# VCA.net
KiCad netlist of a schematic drawn in Altium Designer
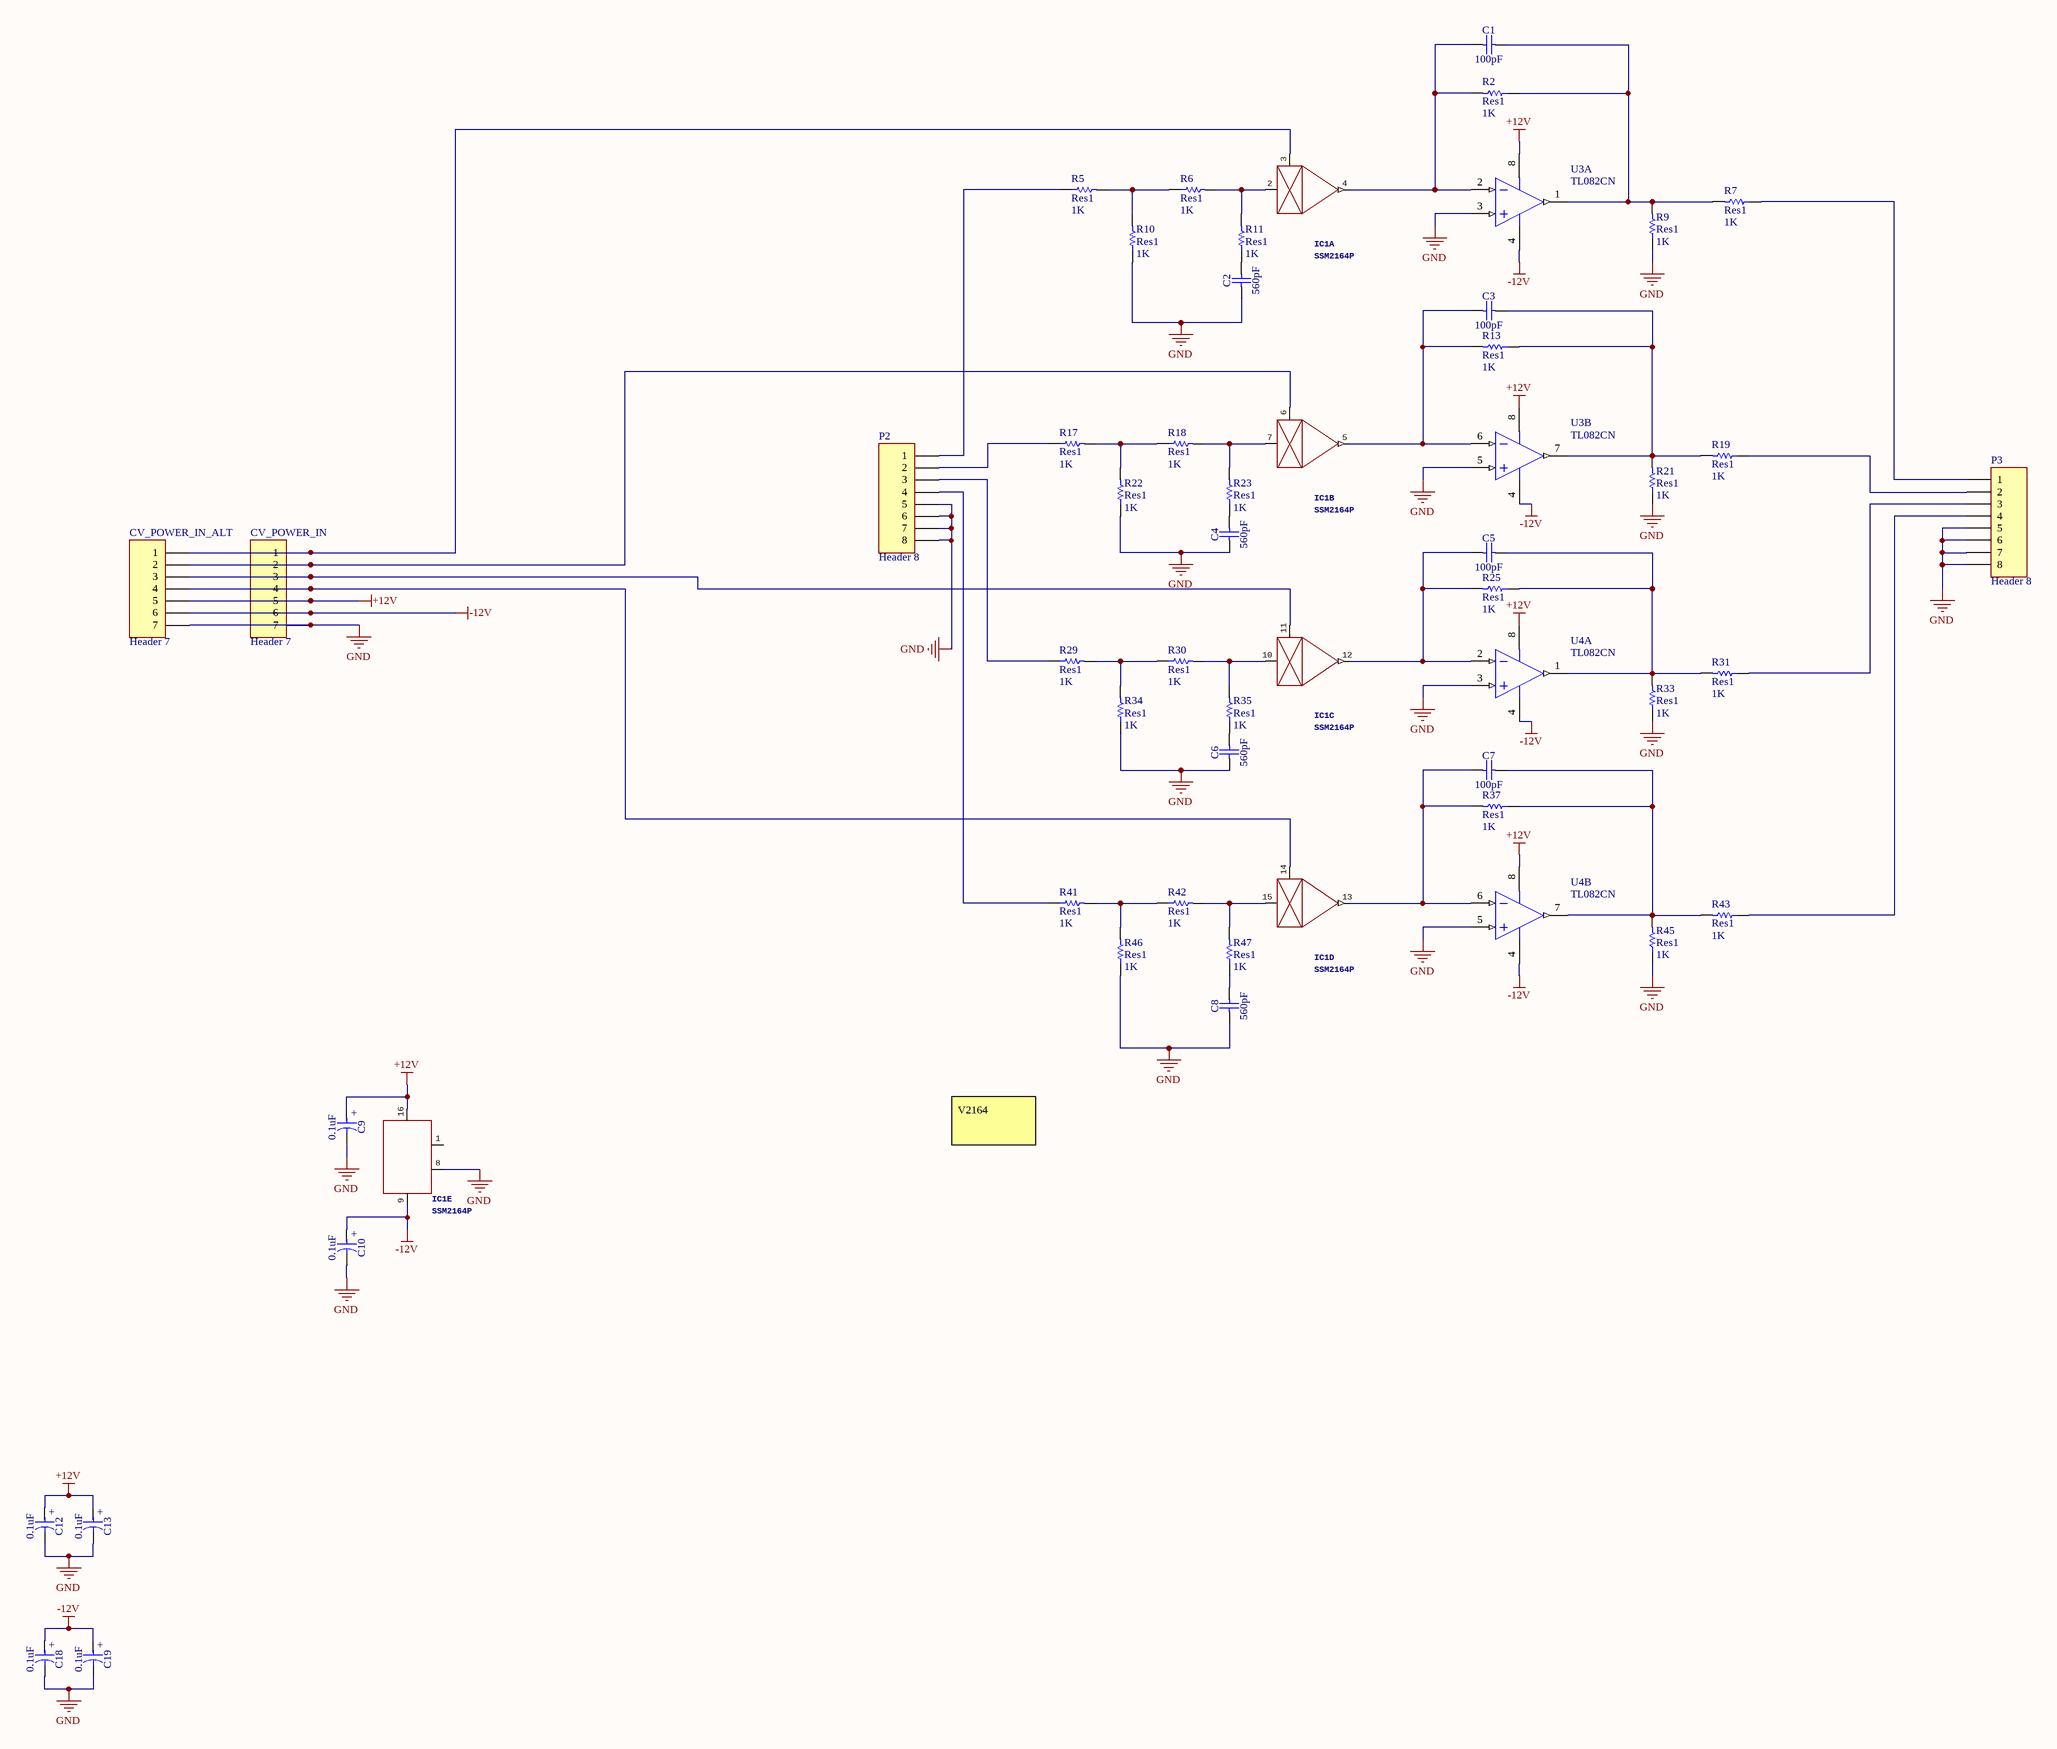
[diagram p0: VCA.SchDoc]

(export (version "E")
  (design (tool "Eeschema 10.0.6"))
  (components
    (comp (ref "C1")
      (value "100pF")
      (footprint "CAPRR508-254X381X584")
      (description "Non-polarised capacitor")
      (fields
        (field (name "PART NUMBER") "CCR_100PF_100V_5%_C0G_508-254X381X584")
        (field (name "VOLTAGE") "100VDC")
        (field (name "AUTHOR") "CERN DEM JLC")
      )
      (libsource (lib "Capacitors") (part "Capacitor - non polarized"))
    )
    (comp (ref "C2")
      (value "560pF")
      (footprint "CAPRR254-254X381X381")
      (description "Non-polarised capacitor")
      (fields
        (field (name "PART NUMBER") "CCR_560PF_100V_5%_C0G_254-254X381X381")
        (field (name "VOLTAGE") "100VDC")
        (field (name "AUTHOR") "CERN DEM JLC")
      )
      (libsource (lib "Capacitors") (part "Capacitor - non polarized"))
    )
    (comp (ref "C3")
      (value "100pF")
      (footprint "CAPRR508-254X381X584")
      (description "Non-polarised capacitor")
      (fields
        (field (name "PART NUMBER") "CCR_100PF_100V_5%_C0G_508-254X381X584")
        (field (name "VOLTAGE") "100VDC")
        (field (name "AUTHOR") "CERN DEM JLC")
      )
      (libsource (lib "Capacitors") (part "Capacitor - non polarized"))
    )
    (comp (ref "C4")
      (value "560pF")
      (footprint "CAPRR254-254X381X381")
      (description "Non-polarised capacitor")
      (fields
        (field (name "PART NUMBER") "CCR_560PF_100V_5%_C0G_254-254X381X381")
        (field (name "VOLTAGE") "100VDC")
        (field (name "AUTHOR") "CERN DEM JLC")
      )
      (libsource (lib "Capacitors") (part "Capacitor - non polarized"))
    )
    (comp (ref "C5")
      (value "100pF")
      (footprint "CAPRR508-254X381X584")
      (description "Non-polarised capacitor")
      (fields
        (field (name "PART NUMBER") "CCR_100PF_100V_5%_C0G_508-254X381X584")
        (field (name "VOLTAGE") "100VDC")
        (field (name "AUTHOR") "CERN DEM JLC")
      )
      (libsource (lib "Capacitors") (part "Capacitor - non polarized"))
    )
    (comp (ref "C6")
      (value "560pF")
      (footprint "CAPRR254-254X381X381")
      (description "Non-polarised capacitor")
      (fields
        (field (name "PART NUMBER") "CCR_560PF_100V_5%_C0G_254-254X381X381")
        (field (name "VOLTAGE") "100VDC")
        (field (name "AUTHOR") "CERN DEM JLC")
      )
      (libsource (lib "Capacitors") (part "Capacitor - non polarized"))
    )
    (comp (ref "C7")
      (value "100pF")
      (footprint "CAPRR508-254X381X584")
      (description "Non-polarised capacitor")
      (fields
        (field (name "PART NUMBER") "CCR_100PF_100V_5%_C0G_508-254X381X584")
        (field (name "VOLTAGE") "100VDC")
        (field (name "AUTHOR") "CERN DEM JLC")
      )
      (libsource (lib "Capacitors") (part "Capacitor - non polarized"))
    )
    (comp (ref "C8")
      (value "560pF")
      (footprint "CAPRR254-254X381X381")
      (description "Non-polarised capacitor")
      (fields
        (field (name "PART NUMBER") "CCR_560PF_100V_5%_C0G_254-254X381X381")
        (field (name "VOLTAGE") "100VDC")
        (field (name "AUTHOR") "CERN DEM JLC")
      )
      (libsource (lib "Capacitors") (part "Capacitor - non polarized"))
    )
    (comp (ref "C9")
      (value "0.1uF")
      (footprint "CAPPRB508-450x850")
      (description "Polarised capacitor")
      (fields
        (field (name "PART NUMBER") "CTEB_0.1UF_35V_10%_508-450X850")
        (field (name "VOLTAGE") "35V")
        (field (name "AUTHOR") "CERN DEM JLC")
      )
      (libsource (lib "Capacitors") (part "Capacitor - polarized"))
    )
    (comp (ref "C10")
      (value "0.1uF")
      (footprint "CAPPRB508-450x850")
      (description "Polarised capacitor")
      (fields
        (field (name "PART NUMBER") "CTEB_0.1UF_35V_10%_508-450X850")
        (field (name "VOLTAGE") "35V")
        (field (name "AUTHOR") "CERN DEM JLC")
      )
      (libsource (lib "Capacitors") (part "Capacitor - polarized"))
    )
    (comp (ref "C12")
      (value "0.1uF")
      (footprint "CAPPRB508-450x850")
      (description "Polarised capacitor")
      (fields
        (field (name "PART NUMBER") "CTEB_0.1UF_35V_10%_508-450X850")
        (field (name "VOLTAGE") "35V")
        (field (name "AUTHOR") "CERN DEM JLC")
      )
      (libsource (lib "Capacitors") (part "Capacitor - polarized"))
    )
    (comp (ref "C13")
      (value "0.1uF")
      (footprint "CAPPRB508-450x850")
      (description "Polarised capacitor")
      (fields
        (field (name "PART NUMBER") "CTEB_0.1UF_35V_10%_508-450X850")
        (field (name "VOLTAGE") "35V")
        (field (name "AUTHOR") "CERN DEM JLC")
      )
      (libsource (lib "Capacitors") (part "Capacitor - polarized"))
    )
    (comp (ref "C18")
      (value "0.1uF")
      (footprint "CAPPRB508-450x850")
      (description "Polarised capacitor")
      (fields
        (field (name "PART NUMBER") "CTEB_0.1UF_35V_10%_508-450X850")
        (field (name "VOLTAGE") "35V")
        (field (name "AUTHOR") "CERN DEM JLC")
      )
      (libsource (lib "Capacitors") (part "Capacitor - polarized"))
    )
    (comp (ref "C19")
      (value "0.1uF")
      (footprint "CAPPRB508-450x850")
      (description "Polarised capacitor")
      (fields
        (field (name "PART NUMBER") "CTEB_0.1UF_35V_10%_508-450X850")
        (field (name "VOLTAGE") "35V")
        (field (name "AUTHOR") "CERN DEM JLC")
      )
      (libsource (lib "Capacitors") (part "Capacitor - polarized"))
    )
    (comp (ref "CV_POWER_IN")
      (value "Header 7")
      (footprint "HDR1X7")
      (description "Header, 7-Pin")
      (fields (field (name "PUBLISHER") "Altium Limited"))
      (libsource (lib "Miscellaneous Connectors") (part "Header 7"))
    )
    (comp (ref "CV_POWER_IN_ALT")
      (value "Header 7")
      (footprint "HDR1X7")
      (description "Header, 7-Pin")
      (libsource (lib "Miscellaneous Connectors") (part "Header 7"))
    )
    (comp (ref "IC1") (value "SSM2164P") (footprint "DIL16") (libsource (lib "ssm2164_2") (part "SSM2164P")))
    (comp (ref "P2")
      (value "Header 8")
      (footprint "HDR1X8")
      (description "Header, 8-Pin")
      (fields (field (name "PUBLISHER") "Altium Limited"))
      (libsource (lib "") (part "Header 8_1"))
    )
    (comp (ref "P3")
      (value "Header 8")
      (footprint "HDR1X8")
      (description "Header, 8-Pin")
      (fields (field (name "PUBLISHER") "Altium Limited"))
      (libsource (lib "Miscellaneous Connectors") (part "Header 8"))
    )
    (comp (ref "R2")
      (value "Res1")
      (footprint "0207/2V")
      (description "Resistor")
      (fields (field (name "ALTIUM_VALUE") "1K") (field (name "PUBLISHER") "Altium Limited"))
      (libsource (lib "Miscellaneous Devices") (part "Res1"))
    )
    (comp (ref "R5")
      (value "Res1")
      (footprint "0207/2V")
      (description "Resistor")
      (fields (field (name "ALTIUM_VALUE") "1K") (field (name "PUBLISHER") "Altium Limited"))
      (libsource (lib "resistor") (part "Res1"))
    )
    (comp (ref "R6")
      (value "Res1")
      (footprint "0207/2V")
      (description "Resistor")
      (fields (field (name "ALTIUM_VALUE") "1K") (field (name "PUBLISHER") "Altium Limited"))
      (libsource (lib "Miscellaneous Devices") (part "Res1"))
    )
    (comp (ref "R7")
      (value "Res1")
      (footprint "0207/2V")
      (description "Resistor")
      (fields (field (name "ALTIUM_VALUE") "1K") (field (name "PUBLISHER") "Altium Limited"))
      (libsource (lib "Miscellaneous Devices") (part "Res1"))
    )
    (comp (ref "R9")
      (value "Res1")
      (footprint "0207/2V")
      (description "Resistor")
      (fields (field (name "ALTIUM_VALUE") "1K") (field (name "PUBLISHER") "Altium Limited"))
      (libsource (lib "Miscellaneous Devices") (part "Res1"))
    )
    (comp (ref "R10")
      (value "Res1")
      (footprint "0207/2V")
      (description "Resistor")
      (fields (field (name "ALTIUM_VALUE") "1K") (field (name "PUBLISHER") "Altium Limited"))
      (libsource (lib "Miscellaneous Devices") (part "Res1"))
    )
    (comp (ref "R11")
      (value "Res1")
      (footprint "0207/2V")
      (description "Resistor")
      (fields (field (name "ALTIUM_VALUE") "1K") (field (name "PUBLISHER") "Altium Limited"))
      (libsource (lib "Miscellaneous Devices") (part "Res1"))
    )
    (comp (ref "R13")
      (value "Res1")
      (footprint "0207/2V")
      (description "Resistor")
      (fields (field (name "ALTIUM_VALUE") "1K") (field (name "PUBLISHER") "Altium Limited"))
      (libsource (lib "Miscellaneous Devices") (part "Res1"))
    )
    (comp (ref "R17")
      (value "Res1")
      (footprint "0207/2V")
      (description "Resistor")
      (fields (field (name "ALTIUM_VALUE") "1K") (field (name "PUBLISHER") "Altium Limited"))
      (libsource (lib "Miscellaneous Devices") (part "Res1"))
    )
    (comp (ref "R18")
      (value "Res1")
      (footprint "0207/2V")
      (description "Resistor")
      (fields (field (name "ALTIUM_VALUE") "1K") (field (name "PUBLISHER") "Altium Limited"))
      (libsource (lib "Miscellaneous Devices") (part "Res1"))
    )
    (comp (ref "R19")
      (value "Res1")
      (footprint "0207/2V")
      (description "Resistor")
      (fields (field (name "ALTIUM_VALUE") "1K") (field (name "PUBLISHER") "Altium Limited"))
      (libsource (lib "Miscellaneous Devices") (part "Res1"))
    )
    (comp (ref "R21")
      (value "Res1")
      (footprint "0207/2V")
      (description "Resistor")
      (fields (field (name "ALTIUM_VALUE") "1K") (field (name "PUBLISHER") "Altium Limited"))
      (libsource (lib "Miscellaneous Devices") (part "Res1"))
    )
    (comp (ref "R22")
      (value "Res1")
      (footprint "0207/2V")
      (description "Resistor")
      (fields (field (name "ALTIUM_VALUE") "1K") (field (name "PUBLISHER") "Altium Limited"))
      (libsource (lib "Miscellaneous Devices") (part "Res1"))
    )
    (comp (ref "R23")
      (value "Res1")
      (footprint "0207/2V")
      (description "Resistor")
      (fields (field (name "ALTIUM_VALUE") "1K") (field (name "PUBLISHER") "Altium Limited"))
      (libsource (lib "Miscellaneous Devices") (part "Res1"))
    )
    (comp (ref "R25")
      (value "Res1")
      (footprint "0207/2V")
      (description "Resistor")
      (fields (field (name "ALTIUM_VALUE") "1K") (field (name "PUBLISHER") "Altium Limited"))
      (libsource (lib "Miscellaneous Devices") (part "Res1"))
    )
    (comp (ref "R29")
      (value "Res1")
      (footprint "0207/2V")
      (description "Resistor")
      (fields (field (name "ALTIUM_VALUE") "1K") (field (name "PUBLISHER") "Altium Limited"))
      (libsource (lib "Miscellaneous Devices") (part "Res1"))
    )
    (comp (ref "R30")
      (value "Res1")
      (footprint "0207/2V")
      (description "Resistor")
      (fields (field (name "ALTIUM_VALUE") "1K") (field (name "PUBLISHER") "Altium Limited"))
      (libsource (lib "Miscellaneous Devices") (part "Res1"))
    )
    (comp (ref "R31")
      (value "Res1")
      (footprint "0207/2V")
      (description "Resistor")
      (fields (field (name "ALTIUM_VALUE") "1K") (field (name "PUBLISHER") "Altium Limited"))
      (libsource (lib "Miscellaneous Devices") (part "Res1"))
    )
    (comp (ref "R33")
      (value "Res1")
      (footprint "0207/2V")
      (description "Resistor")
      (fields (field (name "ALTIUM_VALUE") "1K") (field (name "PUBLISHER") "Altium Limited"))
      (libsource (lib "Miscellaneous Devices") (part "Res1"))
    )
    (comp (ref "R34")
      (value "Res1")
      (footprint "0207/2V")
      (description "Resistor")
      (fields (field (name "ALTIUM_VALUE") "1K") (field (name "PUBLISHER") "Altium Limited"))
      (libsource (lib "Miscellaneous Devices") (part "Res1"))
    )
    (comp (ref "R35")
      (value "Res1")
      (footprint "0207/2V")
      (description "Resistor")
      (fields (field (name "ALTIUM_VALUE") "1K") (field (name "PUBLISHER") "Altium Limited"))
      (libsource (lib "Miscellaneous Devices") (part "Res1"))
    )
    (comp (ref "R37")
      (value "Res1")
      (footprint "0207/2V")
      (description "Resistor")
      (fields (field (name "ALTIUM_VALUE") "1K") (field (name "PUBLISHER") "Altium Limited"))
      (libsource (lib "Miscellaneous Devices") (part "Res1"))
    )
    (comp (ref "R41")
      (value "Res1")
      (footprint "0207/2V")
      (description "Resistor")
      (fields (field (name "ALTIUM_VALUE") "1K") (field (name "PUBLISHER") "Altium Limited"))
      (libsource (lib "Miscellaneous Devices") (part "Res1"))
    )
    (comp (ref "R42")
      (value "Res1")
      (footprint "0207/2V")
      (description "Resistor")
      (fields (field (name "ALTIUM_VALUE") "1K") (field (name "PUBLISHER") "Altium Limited"))
      (libsource (lib "Miscellaneous Devices") (part "Res1"))
    )
    (comp (ref "R43")
      (value "Res1")
      (footprint "0207/2V")
      (description "Resistor")
      (fields (field (name "ALTIUM_VALUE") "1K") (field (name "PUBLISHER") "Altium Limited"))
      (libsource (lib "Miscellaneous Devices") (part "Res1"))
    )
    (comp (ref "R45")
      (value "Res1")
      (footprint "0207/2V")
      (description "Resistor")
      (fields (field (name "ALTIUM_VALUE") "1K") (field (name "PUBLISHER") "Altium Limited"))
      (libsource (lib "Miscellaneous Devices") (part "Res1"))
    )
    (comp (ref "R46")
      (value "Res1")
      (footprint "0207/2V")
      (description "Resistor")
      (fields (field (name "ALTIUM_VALUE") "1K") (field (name "PUBLISHER") "Altium Limited"))
      (libsource (lib "Miscellaneous Devices") (part "Res1"))
    )
    (comp (ref "R47")
      (value "Res1")
      (footprint "0207/2V")
      (description "Resistor")
      (fields (field (name "ALTIUM_VALUE") "1K") (field (name "PUBLISHER") "Altium Limited"))
      (libsource (lib "Miscellaneous Devices") (part "Res1"))
    )
    (comp (ref "U3")
      (value "TL082CN")
      (footprint "STM-N8")
      (fields (field (name "MANUFACTURER") "STMicroelectronics"))
      (libsource (lib "Altium Content Vault") (part "STM-TL082-N8"))
    )
    (comp (ref "U4")
      (value "TL082CN")
      (footprint "STM-N8")
      (fields (field (name "MANUFACTURER") "STMicroelectronics"))
      (libsource (lib "Altium Content Vault") (part "STM-TL082-N8"))
    )
  )
  (nets
    (net (code "1") (name "+12V") (class "Default")
      (node (ref "C12") (pin "1") (pinfunction "1_1") (pintype "passive"))
      (node (ref "C13") (pin "1") (pinfunction "1_1") (pintype "passive"))
      (node (ref "C9") (pin "1") (pinfunction "1_1") (pintype "passive"))
      (node (ref "CV_POWER_IN") (pin "5") (pinfunction "5_5") (pintype "passive"))
      (node (ref "CV_POWER_IN_ALT") (pin "5") (pinfunction "5_5") (pintype "passive"))
      (node (ref "IC1") (pin "16") (pinfunction "V+_16") (pintype "power_in"))
      (node (ref "U3") (pin "8") (pinfunction "VCC+_8") (pintype "power_in"))
      (node (ref "U4") (pin "8") (pinfunction "VCC+_8") (pintype "power_in"))
    )
    (net (code "2") (name "-12V") (class "Default")
      (node (ref "C10") (pin "1") (pinfunction "1_1") (pintype "passive"))
      (node (ref "C18") (pin "1") (pinfunction "1_1") (pintype "passive"))
      (node (ref "C19") (pin "1") (pinfunction "1_1") (pintype "passive"))
      (node (ref "CV_POWER_IN") (pin "6") (pinfunction "6_6") (pintype "passive"))
      (node (ref "CV_POWER_IN_ALT") (pin "6") (pinfunction "6_6") (pintype "passive"))
      (node (ref "IC1") (pin "9") (pinfunction "V-_9") (pintype "power_in"))
      (node (ref "U3") (pin "4") (pinfunction "VCC-_4") (pintype "power_in"))
      (node (ref "U4") (pin "4") (pinfunction "VCC-_4") (pintype "power_in"))
    )
    (net (code "3") (name "GND") (class "Default")
      (node (ref "C10") (pin "2") (pinfunction "2_2") (pintype "passive"))
      (node (ref "C12") (pin "2") (pinfunction "2_2") (pintype "passive"))
      (node (ref "C13") (pin "2") (pinfunction "2_2") (pintype "passive"))
      (node (ref "C18") (pin "2") (pinfunction "2_2") (pintype "passive"))
      (node (ref "C19") (pin "2") (pinfunction "2_2") (pintype "passive"))
      (node (ref "C2") (pin "1") (pinfunction "1_1") (pintype "passive"))
      (node (ref "C4") (pin "1") (pinfunction "1_1") (pintype "passive"))
      (node (ref "C6") (pin "1") (pinfunction "1_1") (pintype "passive"))
      (node (ref "C8") (pin "1") (pinfunction "1_1") (pintype "passive"))
      (node (ref "C9") (pin "2") (pinfunction "2_2") (pintype "passive"))
      (node (ref "CV_POWER_IN") (pin "7") (pinfunction "7_7") (pintype "passive"))
      (node (ref "CV_POWER_IN_ALT") (pin "7") (pinfunction "7_7") (pintype "passive"))
      (node (ref "IC1") (pin "8") (pinfunction "GND_8") (pintype "power_in"))
      (node (ref "P2") (pin "5") (pinfunction "5_5") (pintype "passive"))
      (node (ref "P2") (pin "6") (pinfunction "6_6") (pintype "passive"))
      (node (ref "P2") (pin "7") (pinfunction "7_7") (pintype "passive"))
      (node (ref "P2") (pin "8") (pinfunction "8_8") (pintype "passive"))
      (node (ref "P3") (pin "5") (pinfunction "5_5") (pintype "passive"))
      (node (ref "P3") (pin "6") (pinfunction "6_6") (pintype "passive"))
      (node (ref "P3") (pin "7") (pinfunction "7_7") (pintype "passive"))
      (node (ref "P3") (pin "8") (pinfunction "8_8") (pintype "passive"))
      (node (ref "R10") (pin "1") (pinfunction "1_1") (pintype "passive"))
      (node (ref "R21") (pin "1") (pinfunction "1_1") (pintype "passive"))
      (node (ref "R22") (pin "1") (pinfunction "1_1") (pintype "passive"))
      (node (ref "R33") (pin "1") (pinfunction "1_1") (pintype "passive"))
      (node (ref "R34") (pin "1") (pinfunction "1_1") (pintype "passive"))
      (node (ref "R45") (pin "1") (pinfunction "1_1") (pintype "passive"))
      (node (ref "R46") (pin "1") (pinfunction "1_1") (pintype "passive"))
      (node (ref "R9") (pin "1") (pinfunction "1_1") (pintype "passive"))
      (node (ref "U3") (pin "3") (pinfunction "IN1+_3") (pintype "input"))
      (node (ref "U3") (pin "5") (pinfunction "IN2+_5") (pintype "input"))
      (node (ref "U4") (pin "3") (pinfunction "IN1+_3") (pintype "input"))
      (node (ref "U4") (pin "5") (pinfunction "IN2+_5") (pintype "input"))
    )
    (net (code "4") (name "Net-(C2-Pad2)") (class "Default")
      (node (ref "C2") (pin "2") (pinfunction "2_2") (pintype "passive"))
      (node (ref "R11") (pin "1") (pinfunction "1_1") (pintype "passive"))
    )
    (net (code "5") (name "Net-(C4-Pad2)") (class "Default")
      (node (ref "C4") (pin "2") (pinfunction "2_2") (pintype "passive"))
      (node (ref "R23") (pin "1") (pinfunction "1_1") (pintype "passive"))
    )
    (net (code "6") (name "Net-(C6-Pad2)") (class "Default")
      (node (ref "C6") (pin "2") (pinfunction "2_2") (pintype "passive"))
      (node (ref "R35") (pin "1") (pinfunction "1_1") (pintype "passive"))
    )
    (net (code "7") (name "Net-(C8-Pad2)") (class "Default")
      (node (ref "C8") (pin "2") (pinfunction "2_2") (pintype "passive"))
      (node (ref "R47") (pin "1") (pinfunction "1_1") (pintype "passive"))
    )
    (net (code "8") (name "Net-(IC1A-CTRL)") (class "Default")
      (node (ref "CV_POWER_IN") (pin "1") (pinfunction "1_1") (pintype "passive"))
      (node (ref "CV_POWER_IN_ALT") (pin "1") (pinfunction "1_1") (pintype "passive"))
      (node (ref "IC1") (pin "3") (pinfunction "CTRL_3") (pintype "passive"))
    )
    (net (code "9") (name "Net-(IC1A-IN)") (class "Default")
      (node (ref "IC1") (pin "2") (pinfunction "IN_2") (pintype "passive"))
      (node (ref "R11") (pin "2") (pinfunction "2_2") (pintype "passive"))
      (node (ref "R6") (pin "2") (pinfunction "2_2") (pintype "passive"))
    )
    (net (code "10") (name "Net-(IC1A-OUT)") (class "Default")
      (node (ref "C1") (pin "1") (pinfunction "1_1") (pintype "passive"))
      (node (ref "IC1") (pin "4") (pinfunction "OUT_4") (pintype "output"))
      (node (ref "R2") (pin "2") (pinfunction "2_2") (pintype "passive"))
      (node (ref "U3") (pin "2") (pinfunction "IN1-_2") (pintype "input"))
    )
    (net (code "11") (name "Net-(IC1B-CTRL)") (class "Default")
      (node (ref "CV_POWER_IN") (pin "2") (pinfunction "2_2") (pintype "passive"))
      (node (ref "CV_POWER_IN_ALT") (pin "2") (pinfunction "2_2") (pintype "passive"))
      (node (ref "IC1") (pin "6") (pinfunction "CTRL_6") (pintype "passive"))
    )
    (net (code "12") (name "Net-(IC1B-IN)") (class "Default")
      (node (ref "IC1") (pin "7") (pinfunction "IN_7") (pintype "passive"))
      (node (ref "R18") (pin "2") (pinfunction "2_2") (pintype "passive"))
      (node (ref "R23") (pin "2") (pinfunction "2_2") (pintype "passive"))
    )
    (net (code "13") (name "Net-(IC1B-OUT)") (class "Default")
      (node (ref "C3") (pin "1") (pinfunction "1_1") (pintype "passive"))
      (node (ref "IC1") (pin "5") (pinfunction "OUT_5") (pintype "output"))
      (node (ref "R13") (pin "2") (pinfunction "2_2") (pintype "passive"))
      (node (ref "U3") (pin "6") (pinfunction "IN2-_6") (pintype "input"))
    )
    (net (code "14") (name "Net-(IC1C-CTRL)") (class "Default")
      (node (ref "CV_POWER_IN") (pin "3") (pinfunction "3_3") (pintype "passive"))
      (node (ref "CV_POWER_IN_ALT") (pin "3") (pinfunction "3_3") (pintype "passive"))
      (node (ref "IC1") (pin "11") (pinfunction "CTRL_11") (pintype "passive"))
    )
    (net (code "15") (name "Net-(IC1C-IN)") (class "Default")
      (node (ref "IC1") (pin "10") (pinfunction "IN_10") (pintype "passive"))
      (node (ref "R30") (pin "2") (pinfunction "2_2") (pintype "passive"))
      (node (ref "R35") (pin "2") (pinfunction "2_2") (pintype "passive"))
    )
    (net (code "16") (name "Net-(IC1C-OUT)") (class "Default")
      (node (ref "C5") (pin "1") (pinfunction "1_1") (pintype "passive"))
      (node (ref "IC1") (pin "12") (pinfunction "OUT_12") (pintype "output"))
      (node (ref "R25") (pin "2") (pinfunction "2_2") (pintype "passive"))
      (node (ref "U4") (pin "2") (pinfunction "IN1-_2") (pintype "input"))
    )
    (net (code "17") (name "Net-(IC1D-CTRL)") (class "Default")
      (node (ref "CV_POWER_IN") (pin "4") (pinfunction "4_4") (pintype "passive"))
      (node (ref "CV_POWER_IN_ALT") (pin "4") (pinfunction "4_4") (pintype "passive"))
      (node (ref "IC1") (pin "14") (pinfunction "CTRL_14") (pintype "passive"))
    )
    (net (code "18") (name "Net-(IC1D-IN)") (class "Default")
      (node (ref "IC1") (pin "15") (pinfunction "IN_15") (pintype "passive"))
      (node (ref "R42") (pin "2") (pinfunction "2_2") (pintype "passive"))
      (node (ref "R47") (pin "2") (pinfunction "2_2") (pintype "passive"))
    )
    (net (code "19") (name "Net-(IC1D-OUT)") (class "Default")
      (node (ref "C7") (pin "1") (pinfunction "1_1") (pintype "passive"))
      (node (ref "IC1") (pin "13") (pinfunction "OUT_13") (pintype "output"))
      (node (ref "R37") (pin "2") (pinfunction "2_2") (pintype "passive"))
      (node (ref "U4") (pin "6") (pinfunction "IN2-_6") (pintype "input"))
    )
    (net (code "20") (name "Net-(P2-Pad1)") (class "Default")
      (node (ref "P2") (pin "1") (pinfunction "1_1") (pintype "passive"))
      (node (ref "R5") (pin "1") (pinfunction "1_1") (pintype "passive"))
    )
    (net (code "21") (name "Net-(P2-Pad2)") (class "Default")
      (node (ref "P2") (pin "2") (pinfunction "2_2") (pintype "passive"))
      (node (ref "R17") (pin "1") (pinfunction "1_1") (pintype "passive"))
    )
    (net (code "22") (name "Net-(P2-Pad3)") (class "Default")
      (node (ref "P2") (pin "3") (pinfunction "3_3") (pintype "passive"))
      (node (ref "R29") (pin "1") (pinfunction "1_1") (pintype "passive"))
    )
    (net (code "23") (name "Net-(P2-Pad4)") (class "Default")
      (node (ref "P2") (pin "4") (pinfunction "4_4") (pintype "passive"))
      (node (ref "R41") (pin "1") (pinfunction "1_1") (pintype "passive"))
    )
    (net (code "24") (name "Net-(P3-Pad1)") (class "Default")
      (node (ref "P3") (pin "1") (pinfunction "1_1") (pintype "passive"))
      (node (ref "R7") (pin "1") (pinfunction "1_1") (pintype "passive"))
    )
    (net (code "25") (name "Net-(P3-Pad2)") (class "Default")
      (node (ref "P3") (pin "2") (pinfunction "2_2") (pintype "passive"))
      (node (ref "R19") (pin "1") (pinfunction "1_1") (pintype "passive"))
    )
    (net (code "26") (name "Net-(P3-Pad3)") (class "Default")
      (node (ref "P3") (pin "3") (pinfunction "3_3") (pintype "passive"))
      (node (ref "R31") (pin "1") (pinfunction "1_1") (pintype "passive"))
    )
    (net (code "27") (name "Net-(P3-Pad4)") (class "Default")
      (node (ref "P3") (pin "4") (pinfunction "4_4") (pintype "passive"))
      (node (ref "R43") (pin "1") (pinfunction "1_1") (pintype "passive"))
    )
    (net (code "28") (name "Net-(R10-Pad2)") (class "Default")
      (node (ref "R10") (pin "2") (pinfunction "2_2") (pintype "passive"))
      (node (ref "R5") (pin "2") (pinfunction "2_2") (pintype "passive"))
      (node (ref "R6") (pin "1") (pinfunction "1_1") (pintype "passive"))
    )
    (net (code "29") (name "Net-(R17-Pad2)") (class "Default")
      (node (ref "R17") (pin "2") (pinfunction "2_2") (pintype "passive"))
      (node (ref "R18") (pin "1") (pinfunction "1_1") (pintype "passive"))
      (node (ref "R22") (pin "2") (pinfunction "2_2") (pintype "passive"))
    )
    (net (code "30") (name "Net-(R29-Pad2)") (class "Default")
      (node (ref "R29") (pin "2") (pinfunction "2_2") (pintype "passive"))
      (node (ref "R30") (pin "1") (pinfunction "1_1") (pintype "passive"))
      (node (ref "R34") (pin "2") (pinfunction "2_2") (pintype "passive"))
    )
    (net (code "31") (name "Net-(R41-Pad2)") (class "Default")
      (node (ref "R41") (pin "2") (pinfunction "2_2") (pintype "passive"))
      (node (ref "R42") (pin "1") (pinfunction "1_1") (pintype "passive"))
      (node (ref "R46") (pin "2") (pinfunction "2_2") (pintype "passive"))
    )
    (net (code "32") (name "Net-(U3A-OUT1)") (class "Default")
      (node (ref "C1") (pin "2") (pinfunction "2_2") (pintype "passive"))
      (node (ref "R2") (pin "1") (pinfunction "1_1") (pintype "passive"))
      (node (ref "R7") (pin "2") (pinfunction "2_2") (pintype "passive"))
      (node (ref "R9") (pin "2") (pinfunction "2_2") (pintype "passive"))
      (node (ref "U3") (pin "1") (pinfunction "OUT1_1") (pintype "output"))
    )
    (net (code "33") (name "Net-(U3B-OUT2)") (class "Default")
      (node (ref "C3") (pin "2") (pinfunction "2_2") (pintype "passive"))
      (node (ref "R13") (pin "1") (pinfunction "1_1") (pintype "passive"))
      (node (ref "R19") (pin "2") (pinfunction "2_2") (pintype "passive"))
      (node (ref "R21") (pin "2") (pinfunction "2_2") (pintype "passive"))
      (node (ref "U3") (pin "7") (pinfunction "OUT2_7") (pintype "output"))
    )
    (net (code "34") (name "Net-(U4A-OUT1)") (class "Default")
      (node (ref "C5") (pin "2") (pinfunction "2_2") (pintype "passive"))
      (node (ref "R25") (pin "1") (pinfunction "1_1") (pintype "passive"))
      (node (ref "R31") (pin "2") (pinfunction "2_2") (pintype "passive"))
      (node (ref "R33") (pin "2") (pinfunction "2_2") (pintype "passive"))
      (node (ref "U4") (pin "1") (pinfunction "OUT1_1") (pintype "output"))
    )
    (net (code "35") (name "Net-(U4B-OUT2)") (class "Default")
      (node (ref "C7") (pin "2") (pinfunction "2_2") (pintype "passive"))
      (node (ref "R37") (pin "1") (pinfunction "1_1") (pintype "passive"))
      (node (ref "R43") (pin "2") (pinfunction "2_2") (pintype "passive"))
      (node (ref "R45") (pin "2") (pinfunction "2_2") (pintype "passive"))
      (node (ref "U4") (pin "7") (pinfunction "OUT2_7") (pintype "output"))
    )
    (net (code "36") (name "unconnected-(IC1E-MODE-Pad1)") (class "Default")
      (node (ref "IC1") (pin "1") (pinfunction "MODE_1") (pintype "passive"))
    )
  )
)
